# protel_lowlevel_shield.net
KiCad netlist of a schematic drawn in Altium Designer
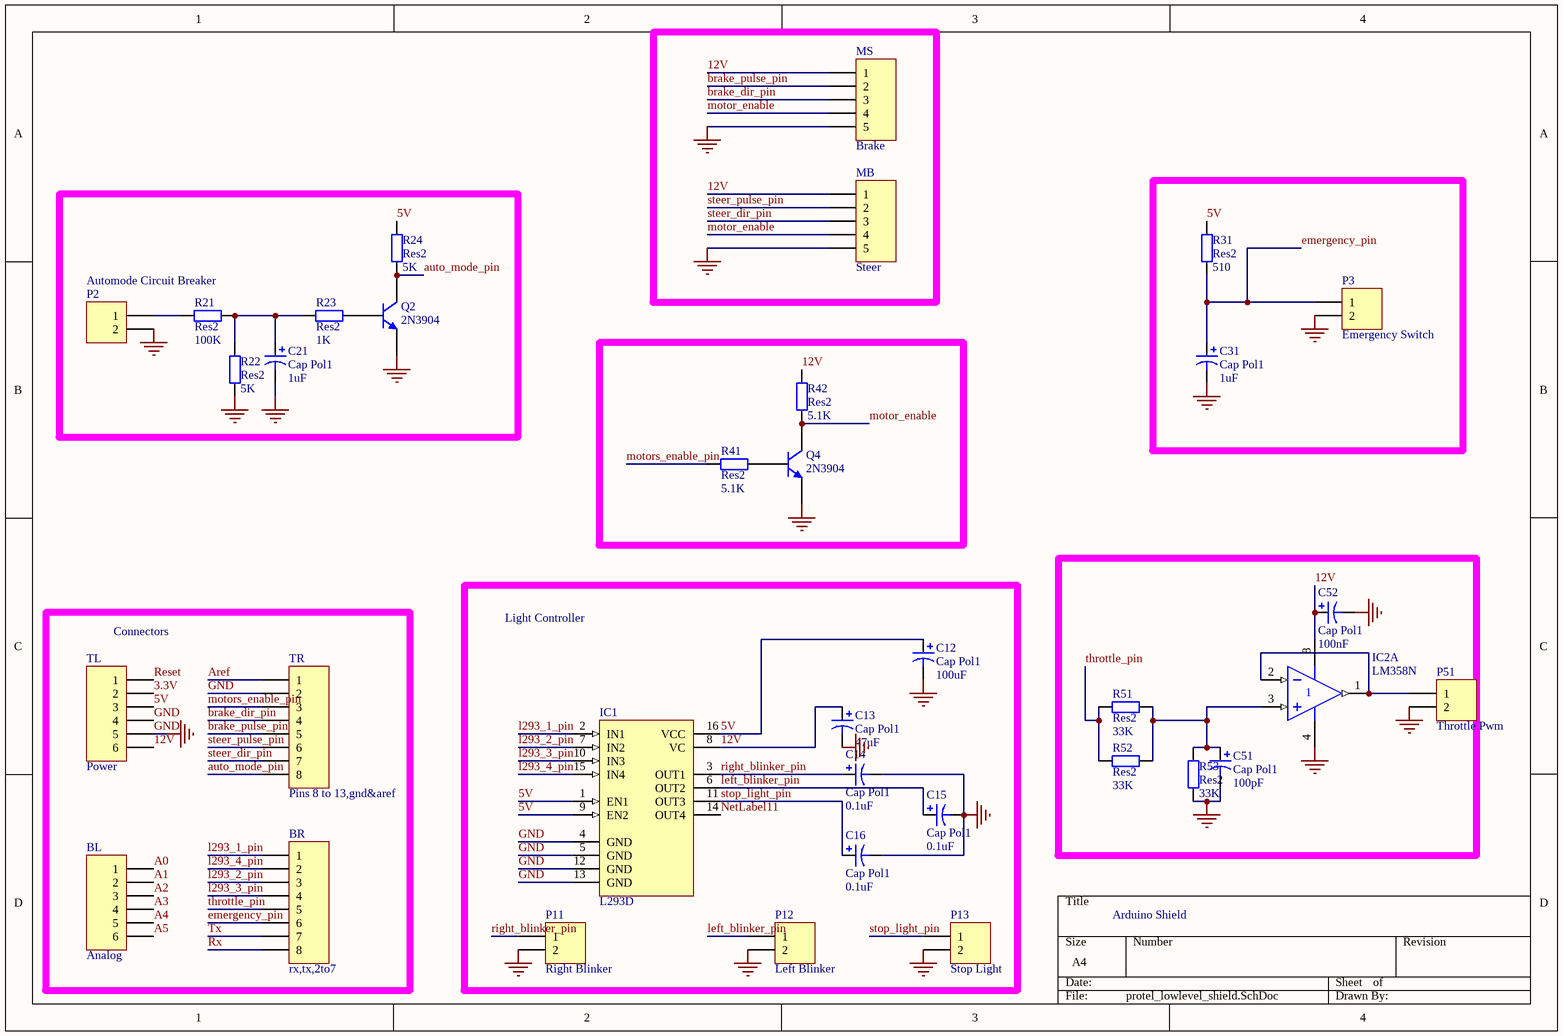
[diagram p0: protel_lowlevel_shield.SchDoc]

(export (version "E")
  (design (tool "Eeschema 10.0.6"))
  (components
    (comp (ref "BL")
      (value "Analog")
      (footprint "HDR1X6")
      (description "Header, 6-Pin, Right Angle")
      (fields (field (name "PUBLISHER") "Altium Limited"))
      (libsource (lib "Miscellaneous Connectors") (part "Header 6H"))
    )
    (comp (ref "BR")
      (value "rx,tx,2to7")
      (footprint "HDR1X8")
      (description "Header, 8-Pin, Right Angle")
      (fields (field (name "PUBLISHER") "Altium Limited"))
      (libsource (lib "Miscellaneous Connectors") (part "Header 8H"))
    )
    (comp (ref "C12")
      (value "Cap Pol1")
      (footprint "CAPPR5-5x5")
      (description "Polarized Capacitor (Radial)")
      (fields (field (name "ALTIUM_VALUE") "100uF") (field (name "PUBLISHER") "Altium Limited"))
      (libsource (lib "Miscellaneous Devices") (part "Cap Pol1"))
    )
    (comp (ref "C13")
      (value "Cap Pol1")
      (footprint "CAPPR5-5x5")
      (description "Polarized Capacitor (Radial)")
      (fields (field (name "ALTIUM_VALUE") "47uF") (field (name "PUBLISHER") "Altium Limited"))
      (libsource (lib "Miscellaneous Devices") (part "Cap Pol1"))
    )
    (comp (ref "C14")
      (value "Cap Pol1")
      (footprint "CAPPR5-5x5")
      (description "Polarized Capacitor (Radial)")
      (fields (field (name "ALTIUM_VALUE") "0.1uF") (field (name "PUBLISHER") "Altium Limited"))
      (libsource (lib "Miscellaneous Devices") (part "Cap Pol1"))
    )
    (comp (ref "C15")
      (value "Cap Pol1")
      (footprint "CAPPR5-5x5")
      (description "Polarized Capacitor (Radial)")
      (fields (field (name "ALTIUM_VALUE") "0.1uF") (field (name "PUBLISHER") "Altium Limited"))
      (libsource (lib "Miscellaneous Devices") (part "Cap Pol1"))
    )
    (comp (ref "C16")
      (value "Cap Pol1")
      (footprint "CAPPR5-5x5")
      (description "Polarized Capacitor (Radial)")
      (fields (field (name "ALTIUM_VALUE") "0.1uF") (field (name "PUBLISHER") "Altium Limited"))
      (libsource (lib "Miscellaneous Devices") (part "Cap Pol1"))
    )
    (comp (ref "C21")
      (value "Cap Pol1")
      (footprint "CAPPR5-5x5")
      (description "Polarized Capacitor (Radial)")
      (fields (field (name "ALTIUM_VALUE") "1uF") (field (name "PUBLISHER") "Altium Limited"))
      (libsource (lib "Miscellaneous Devices") (part "Cap Pol1"))
    )
    (comp (ref "C31")
      (value "Cap Pol1")
      (footprint "CAPPR5-5x5")
      (description "Polarized Capacitor (Radial)")
      (fields (field (name "ALTIUM_VALUE") "1uF") (field (name "PUBLISHER") "Altium Limited"))
      (libsource (lib "Miscellaneous Devices") (part "Cap Pol1"))
    )
    (comp (ref "C51")
      (value "Cap Pol1")
      (footprint "CAPPR5-5x5")
      (description "Polarized Capacitor (Radial)")
      (fields (field (name "ALTIUM_VALUE") "100pF") (field (name "PUBLISHER") "Altium Limited"))
      (libsource (lib "Miscellaneous Devices") (part "Cap Pol1"))
    )
    (comp (ref "C52")
      (value "Cap Pol1")
      (footprint "CAPPR5-5x5")
      (description "Polarized Capacitor (Radial)")
      (fields (field (name "ALTIUM_VALUE") "100nF") (field (name "PUBLISHER") "Altium Limited"))
      (libsource (lib "Miscellaneous Devices") (part "Cap Pol1"))
    )
    (comp (ref "IC1")
      (value "L293D")
      (footprint "DIP16")
      (description "Push-Pull Four Channel Driver With Diode")
      (fields (field (name "PUBLISHER") "Altium Limited"))
      (libsource (lib "ST Interface DC & Stepper Motor Controller") (part "L293D"))
    )
    (comp (ref "IC2")
      (value "LM358N")
      (footprint "626-05")
      (description "Dual Low-Power Operational Amplifier")
      (fields (field (name "PUBLISHER") "Altium Limited"))
      (libsource (lib "Motorola Amplifier Operational Amplifier") (part "LM358N"))
    )
    (comp (ref "MB")
      (value "Steer")
      (footprint "HDR1X5H")
      (description "Header, 5-Pin, Right Angle")
      (fields (field (name "PUBLISHER") "Altium Limited"))
      (libsource (lib "Miscellaneous Connectors") (part "Header 5H"))
    )
    (comp (ref "MS")
      (value "Brake")
      (footprint "HDR1X5H")
      (description "Header, 5-Pin, Right Angle")
      (fields (field (name "PUBLISHER") "Altium Limited"))
      (libsource (lib "Miscellaneous Connectors") (part "Header 5H"))
    )
    (comp (ref "P2")
      (value "Automode Circuit Breaker")
      (footprint "HDR1X2")
      (description "Header, 2-Pin")
      (fields (field (name "PUBLISHER") "Altium Limited"))
      (libsource (lib "") (part "Header 2_1"))
    )
    (comp (ref "P3")
      (value "Emergency Switch")
      (footprint "HDR1X2")
      (description "Header, 2-Pin")
      (fields (field (name "PUBLISHER") "Altium Limited"))
      (libsource (lib "Miscellaneous Connectors") (part "Header 2"))
    )
    (comp (ref "P11")
      (value "Right Blinker")
      (footprint "HDR1X2")
      (description "Header, 2-Pin")
      (fields (field (name "PUBLISHER") "Altium Limited"))
      (libsource (lib "Miscellaneous Connectors") (part "Header 2"))
    )
    (comp (ref "P12")
      (value "Left Blinker")
      (footprint "HDR1X2")
      (description "Header, 2-Pin")
      (fields (field (name "PUBLISHER") "Altium Limited"))
      (libsource (lib "Miscellaneous Connectors") (part "Header 2"))
    )
    (comp (ref "P13")
      (value "Stop Light")
      (footprint "HDR1X2")
      (description "Header, 2-Pin")
      (fields (field (name "PUBLISHER") "Altium Limited"))
      (libsource (lib "Miscellaneous Connectors") (part "Header 2"))
    )
    (comp (ref "P51")
      (value "Throttle Pwm")
      (footprint "HDR1X2")
      (description "Header, 2-Pin")
      (fields (field (name "PUBLISHER") "Altium Limited"))
      (libsource (lib "Miscellaneous Connectors") (part "Header 2"))
    )
    (comp (ref "Q2")
      (value "2N3904")
      (footprint "CAN-3/Y1.5")
      (description "General Purpose Transistor NPN Silicon")
      (fields (field (name "PUBLISHER") "Altium Limited"))
      (libsource (lib "Motorola Discrete BJT") (part "2N2222"))
    )
    (comp (ref "Q4")
      (value "2N3904")
      (footprint "CAN-3/D5.9")
      (description "General Purpose Transistor NPN Silicon")
      (fields (field (name "PUBLISHER") "Altium Limited"))
      (libsource (lib "Motorola Discrete BJT") (part "2N2222"))
    )
    (comp (ref "R21")
      (value "Res2")
      (footprint "AXIAL-0.4")
      (description "Resistor")
      (fields (field (name "ALTIUM_VALUE") "100K") (field (name "PUBLISHER") "Altium Limited"))
      (libsource (lib "Miscellaneous Devices") (part "Res2"))
    )
    (comp (ref "R22")
      (value "Res2")
      (footprint "AXIAL-0.4")
      (description "Resistor")
      (fields (field (name "ALTIUM_VALUE") "5K") (field (name "PUBLISHER") "Altium Limited"))
      (libsource (lib "") (part "Res2_1"))
    )
    (comp (ref "R23")
      (value "Res2")
      (footprint "AXIAL-0.4")
      (description "Resistor")
      (fields (field (name "ALTIUM_VALUE") "1K") (field (name "PUBLISHER") "Altium Limited"))
      (libsource (lib "Miscellaneous Devices") (part "Res2"))
    )
    (comp (ref "R24")
      (value "Res2")
      (footprint "AXIAL-0.4")
      (description "Resistor")
      (fields (field (name "ALTIUM_VALUE") "5K") (field (name "PUBLISHER") "Altium Limited"))
      (libsource (lib "") (part "Res2_1"))
    )
    (comp (ref "R31")
      (value "Res2")
      (footprint "AXIAL-0.4")
      (description "Resistor")
      (fields (field (name "ALTIUM_VALUE") "510") (field (name "PUBLISHER") "Altium Limited"))
      (libsource (lib "") (part "Res2_1"))
    )
    (comp (ref "R41")
      (value "Res2")
      (footprint "AXIAL-0.4")
      (description "Resistor")
      (fields (field (name "ALTIUM_VALUE") "5.1K") (field (name "PUBLISHER") "Altium Limited"))
      (libsource (lib "Miscellaneous Devices") (part "Res2"))
    )
    (comp (ref "R42")
      (value "Res2")
      (footprint "AXIAL-0.4")
      (description "Resistor")
      (fields (field (name "ALTIUM_VALUE") "5.1K") (field (name "PUBLISHER") "Altium Limited"))
      (libsource (lib "") (part "Res2_1"))
    )
    (comp (ref "R51")
      (value "Res2")
      (footprint "AXIAL-0.4")
      (description "Resistor")
      (fields (field (name "ALTIUM_VALUE") "33K") (field (name "PUBLISHER") "Altium Limited"))
      (libsource (lib "Miscellaneous Devices") (part "Res2"))
    )
    (comp (ref "R52")
      (value "Res2")
      (footprint "AXIAL-0.4")
      (description "Resistor")
      (fields (field (name "ALTIUM_VALUE") "33K") (field (name "PUBLISHER") "Altium Limited"))
      (libsource (lib "Miscellaneous Devices") (part "Res2"))
    )
    (comp (ref "R53")
      (value "Res2")
      (footprint "AXIAL-0.4")
      (description "Resistor")
      (fields (field (name "ALTIUM_VALUE") "33K") (field (name "PUBLISHER") "Altium Limited"))
      (libsource (lib "") (part "Res2_1"))
    )
    (comp (ref "TL")
      (value "Power")
      (footprint "HDR1X6")
      (description "Header, 6-Pin, Right Angle")
      (fields (field (name "PUBLISHER") "Altium Limited"))
      (libsource (lib "Miscellaneous Connectors") (part "Header 6H"))
    )
    (comp (ref "TR")
      (value "Pins 8 to 13,gnd&aref")
      (footprint "HDR1X8")
      (description "Header, 8-Pin, Right Angle")
      (fields (field (name "PUBLISHER") "Altium Limited"))
      (libsource (lib "Miscellaneous Connectors") (part "Header 8H"))
    )
  )
  (nets
    (net (code "1") (name "/3.3V") (class "Default")
      (node (ref "TL") (pin "2") (pinfunction "2_2") (pintype "passive"))
    )
    (net (code "2") (name "/5V") (class "Default")
      (node (ref "C12") (pin "1") (pinfunction "1_1") (pintype "passive"))
      (node (ref "IC1") (pin "1") (pinfunction "EN1_1") (pintype "input"))
      (node (ref "IC1") (pin "16") (pinfunction "VCC_16") (pintype "power_in"))
      (node (ref "IC1") (pin "9") (pinfunction "EN2_9") (pintype "input"))
      (node (ref "R24") (pin "2") (pinfunction "2_2") (pintype "passive"))
      (node (ref "R31") (pin "2") (pinfunction "2_2") (pintype "passive"))
      (node (ref "TL") (pin "3") (pinfunction "3_3") (pintype "passive"))
    )
    (net (code "3") (name "/12V") (class "Default")
      (node (ref "C13") (pin "1") (pinfunction "1_1") (pintype "passive"))
      (node (ref "C52") (pin "1") (pinfunction "1_1") (pintype "passive"))
      (node (ref "IC1") (pin "8") (pinfunction "VC_8") (pintype "power_in"))
      (node (ref "IC2") (pin "8") (pinfunction "V+_8") (pintype "power_in"))
      (node (ref "MB") (pin "1") (pinfunction "1_1") (pintype "passive"))
      (node (ref "MS") (pin "1") (pinfunction "1_1") (pintype "passive"))
      (node (ref "R42") (pin "2") (pinfunction "2_2") (pintype "passive"))
      (node (ref "TL") (pin "6") (pinfunction "6_6") (pintype "passive"))
    )
    (net (code "4") (name "/A0") (class "Default")
      (node (ref "BL") (pin "1") (pinfunction "1_1") (pintype "passive"))
    )
    (net (code "5") (name "/A1") (class "Default")
      (node (ref "BL") (pin "2") (pinfunction "2_2") (pintype "passive"))
    )
    (net (code "6") (name "/A2") (class "Default")
      (node (ref "BL") (pin "3") (pinfunction "3_3") (pintype "passive"))
    )
    (net (code "7") (name "/A3") (class "Default")
      (node (ref "BL") (pin "4") (pinfunction "4_4") (pintype "passive"))
    )
    (net (code "8") (name "/A4") (class "Default")
      (node (ref "BL") (pin "5") (pinfunction "5_5") (pintype "passive"))
    )
    (net (code "9") (name "/A5") (class "Default")
      (node (ref "BL") (pin "6") (pinfunction "6_6") (pintype "passive"))
    )
    (net (code "10") (name "/Aref") (class "Default")
      (node (ref "TR") (pin "1") (pinfunction "1_1") (pintype "passive"))
    )
    (net (code "11") (name "/NetLabel11") (class "Default")
      (node (ref "IC1") (pin "14") (pinfunction "OUT4_14") (pintype "tri_state"))
    )
    (net (code "12") (name "/Reset") (class "Default")
      (node (ref "TL") (pin "1") (pinfunction "1_1") (pintype "passive"))
    )
    (net (code "13") (name "/Rx") (class "Default")
      (node (ref "BR") (pin "8") (pinfunction "8_8") (pintype "passive"))
    )
    (net (code "14") (name "/Tx") (class "Default")
      (node (ref "BR") (pin "7") (pinfunction "7_7") (pintype "passive"))
    )
    (net (code "15") (name "/auto_mode_pin") (class "Default")
      (node (ref "Q2") (pin "3") (pinfunction "C_3") (pintype "passive"))
      (node (ref "R24") (pin "1") (pinfunction "1_1") (pintype "passive"))
      (node (ref "TR") (pin "8") (pinfunction "8_8") (pintype "passive"))
    )
    (net (code "16") (name "/brake_dir_pin") (class "Default")
      (node (ref "MS") (pin "3") (pinfunction "3_3") (pintype "passive"))
      (node (ref "TR") (pin "4") (pinfunction "4_4") (pintype "passive"))
    )
    (net (code "17") (name "/brake_pulse_pin") (class "Default")
      (node (ref "MS") (pin "2") (pinfunction "2_2") (pintype "passive"))
      (node (ref "TR") (pin "5") (pinfunction "5_5") (pintype "passive"))
    )
    (net (code "18") (name "/emergency_pin") (class "Default")
      (node (ref "BR") (pin "6") (pinfunction "6_6") (pintype "passive"))
      (node (ref "C31") (pin "1") (pinfunction "1_1") (pintype "passive"))
      (node (ref "P3") (pin "1") (pinfunction "1_1") (pintype "passive"))
      (node (ref "R31") (pin "1") (pinfunction "1_1") (pintype "passive"))
    )
    (net (code "19") (name "/l293_1_pin") (class "Default")
      (node (ref "BR") (pin "1") (pinfunction "1_1") (pintype "passive"))
      (node (ref "IC1") (pin "2") (pinfunction "IN1_2") (pintype "input"))
    )
    (net (code "20") (name "/l293_2_pin") (class "Default")
      (node (ref "BR") (pin "3") (pinfunction "3_3") (pintype "passive"))
      (node (ref "IC1") (pin "7") (pinfunction "IN2_7") (pintype "input"))
    )
    (net (code "21") (name "/l293_3_pin") (class "Default")
      (node (ref "BR") (pin "4") (pinfunction "4_4") (pintype "passive"))
      (node (ref "IC1") (pin "10") (pinfunction "IN3_10") (pintype "input"))
    )
    (net (code "22") (name "/l293_4_pin") (class "Default")
      (node (ref "BR") (pin "2") (pinfunction "2_2") (pintype "passive"))
      (node (ref "IC1") (pin "15") (pinfunction "IN4_15") (pintype "input"))
    )
    (net (code "23") (name "/left_blinker_pin") (class "Default")
      (node (ref "C15") (pin "1") (pinfunction "1_1") (pintype "passive"))
      (node (ref "IC1") (pin "6") (pinfunction "OUT2_6") (pintype "tri_state"))
      (node (ref "P12") (pin "1") (pinfunction "1_1") (pintype "passive"))
    )
    (net (code "24") (name "/motor_enable") (class "Default")
      (node (ref "MB") (pin "4") (pinfunction "4_4") (pintype "passive"))
      (node (ref "MS") (pin "4") (pinfunction "4_4") (pintype "passive"))
      (node (ref "Q4") (pin "3") (pinfunction "C_3") (pintype "passive"))
      (node (ref "R42") (pin "1") (pinfunction "1_1") (pintype "passive"))
    )
    (net (code "25") (name "/motors_enable_pin") (class "Default")
      (node (ref "R41") (pin "1") (pinfunction "1_1") (pintype "passive"))
      (node (ref "TR") (pin "3") (pinfunction "3_3") (pintype "passive"))
    )
    (net (code "26") (name "/right_blinker_pin") (class "Default")
      (node (ref "C14") (pin "1") (pinfunction "1_1") (pintype "passive"))
      (node (ref "IC1") (pin "3") (pinfunction "OUT1_3") (pintype "tri_state"))
      (node (ref "P11") (pin "1") (pinfunction "1_1") (pintype "passive"))
    )
    (net (code "27") (name "/steer_dir_pin") (class "Default")
      (node (ref "MB") (pin "3") (pinfunction "3_3") (pintype "passive"))
      (node (ref "TR") (pin "7") (pinfunction "7_7") (pintype "passive"))
    )
    (net (code "28") (name "/steer_pulse_pin") (class "Default")
      (node (ref "MB") (pin "2") (pinfunction "2_2") (pintype "passive"))
      (node (ref "TR") (pin "6") (pinfunction "6_6") (pintype "passive"))
    )
    (net (code "29") (name "/stop_light_pin") (class "Default")
      (node (ref "C16") (pin "1") (pinfunction "1_1") (pintype "passive"))
      (node (ref "IC1") (pin "11") (pinfunction "OUT3_11") (pintype "tri_state"))
      (node (ref "P13") (pin "1") (pinfunction "1_1") (pintype "passive"))
    )
    (net (code "30") (name "/throttle_pin") (class "Default")
      (node (ref "BR") (pin "5") (pinfunction "5_5") (pintype "passive"))
      (node (ref "R51") (pin "1") (pinfunction "1_1") (pintype "passive"))
      (node (ref "R52") (pin "1") (pinfunction "1_1") (pintype "passive"))
    )
    (net (code "31") (name "GND") (class "Default")
      (node (ref "C12") (pin "2") (pinfunction "2_2") (pintype "passive"))
      (node (ref "C13") (pin "2") (pinfunction "2_2") (pintype "passive"))
      (node (ref "C14") (pin "2") (pinfunction "2_2") (pintype "passive"))
      (node (ref "C15") (pin "2") (pinfunction "2_2") (pintype "passive"))
      (node (ref "C16") (pin "2") (pinfunction "2_2") (pintype "passive"))
      (node (ref "C21") (pin "2") (pinfunction "2_2") (pintype "passive"))
      (node (ref "C31") (pin "2") (pinfunction "2_2") (pintype "passive"))
      (node (ref "C51") (pin "2") (pinfunction "2_2") (pintype "passive"))
      (node (ref "C52") (pin "2") (pinfunction "2_2") (pintype "passive"))
      (node (ref "IC1") (pin "12") (pinfunction "GND_12") (pintype "power_in"))
      (node (ref "IC1") (pin "13") (pinfunction "GND_13") (pintype "power_in"))
      (node (ref "IC1") (pin "4") (pinfunction "GND_4") (pintype "power_in"))
      (node (ref "IC1") (pin "5") (pinfunction "GND_5") (pintype "power_in"))
      (node (ref "IC2") (pin "4") (pinfunction "V-_4") (pintype "power_in"))
      (node (ref "MB") (pin "5") (pinfunction "5_5") (pintype "passive"))
      (node (ref "MS") (pin "5") (pinfunction "5_5") (pintype "passive"))
      (node (ref "P11") (pin "2") (pinfunction "2_2") (pintype "passive"))
      (node (ref "P12") (pin "2") (pinfunction "2_2") (pintype "passive"))
      (node (ref "P13") (pin "2") (pinfunction "2_2") (pintype "passive"))
      (node (ref "P2") (pin "2") (pinfunction "2_2") (pintype "passive"))
      (node (ref "P3") (pin "2") (pinfunction "2_2") (pintype "passive"))
      (node (ref "P51") (pin "2") (pinfunction "2_2") (pintype "passive"))
      (node (ref "Q2") (pin "1") (pinfunction "E_1") (pintype "passive"))
      (node (ref "Q4") (pin "1") (pinfunction "E_1") (pintype "passive"))
      (node (ref "R22") (pin "1") (pinfunction "1_1") (pintype "passive"))
      (node (ref "R53") (pin "1") (pinfunction "1_1") (pintype "passive"))
      (node (ref "TL") (pin "4") (pinfunction "4_4") (pintype "passive"))
      (node (ref "TL") (pin "5") (pinfunction "5_5") (pintype "passive"))
      (node (ref "TR") (pin "2") (pinfunction "2_2") (pintype "passive"))
    )
    (net (code "32") (name "Net-(C21-Pad1)") (class "Default")
      (node (ref "C21") (pin "1") (pinfunction "1_1") (pintype "passive"))
      (node (ref "R21") (pin "2") (pinfunction "2_2") (pintype "passive"))
      (node (ref "R22") (pin "2") (pinfunction "2_2") (pintype "passive"))
      (node (ref "R23") (pin "1") (pinfunction "1_1") (pintype "passive"))
    )
    (net (code "33") (name "Net-(IC2A-IN+)") (class "Default")
      (node (ref "C51") (pin "1") (pinfunction "1_1") (pintype "passive"))
      (node (ref "IC2") (pin "3") (pinfunction "IN+_3") (pintype "input"))
      (node (ref "R51") (pin "2") (pinfunction "2_2") (pintype "passive"))
      (node (ref "R52") (pin "2") (pinfunction "2_2") (pintype "passive"))
      (node (ref "R53") (pin "2") (pinfunction "2_2") (pintype "passive"))
    )
    (net (code "34") (name "Net-(IC2A-IN-)") (class "Default")
      (node (ref "IC2") (pin "1") (pinfunction "OUT_1") (pintype "output"))
      (node (ref "IC2") (pin "2") (pinfunction "IN-_2") (pintype "input"))
      (node (ref "P51") (pin "1") (pinfunction "1_1") (pintype "passive"))
    )
    (net (code "35") (name "Net-(P2-Pad1)") (class "Default")
      (node (ref "P2") (pin "1") (pinfunction "1_1") (pintype "passive"))
      (node (ref "R21") (pin "1") (pinfunction "1_1") (pintype "passive"))
    )
    (net (code "36") (name "Net-(Q2-B)") (class "Default")
      (node (ref "Q2") (pin "2") (pinfunction "B_2") (pintype "passive"))
      (node (ref "R23") (pin "2") (pinfunction "2_2") (pintype "passive"))
    )
    (net (code "37") (name "Net-(Q4-B)") (class "Default")
      (node (ref "Q4") (pin "2") (pinfunction "B_2") (pintype "passive"))
      (node (ref "R41") (pin "2") (pinfunction "2_2") (pintype "passive"))
    )
  )
)
